# PROIECT_OPEN_READER_v53.net
KiCad netlist of a schematic drawn in EAGLE
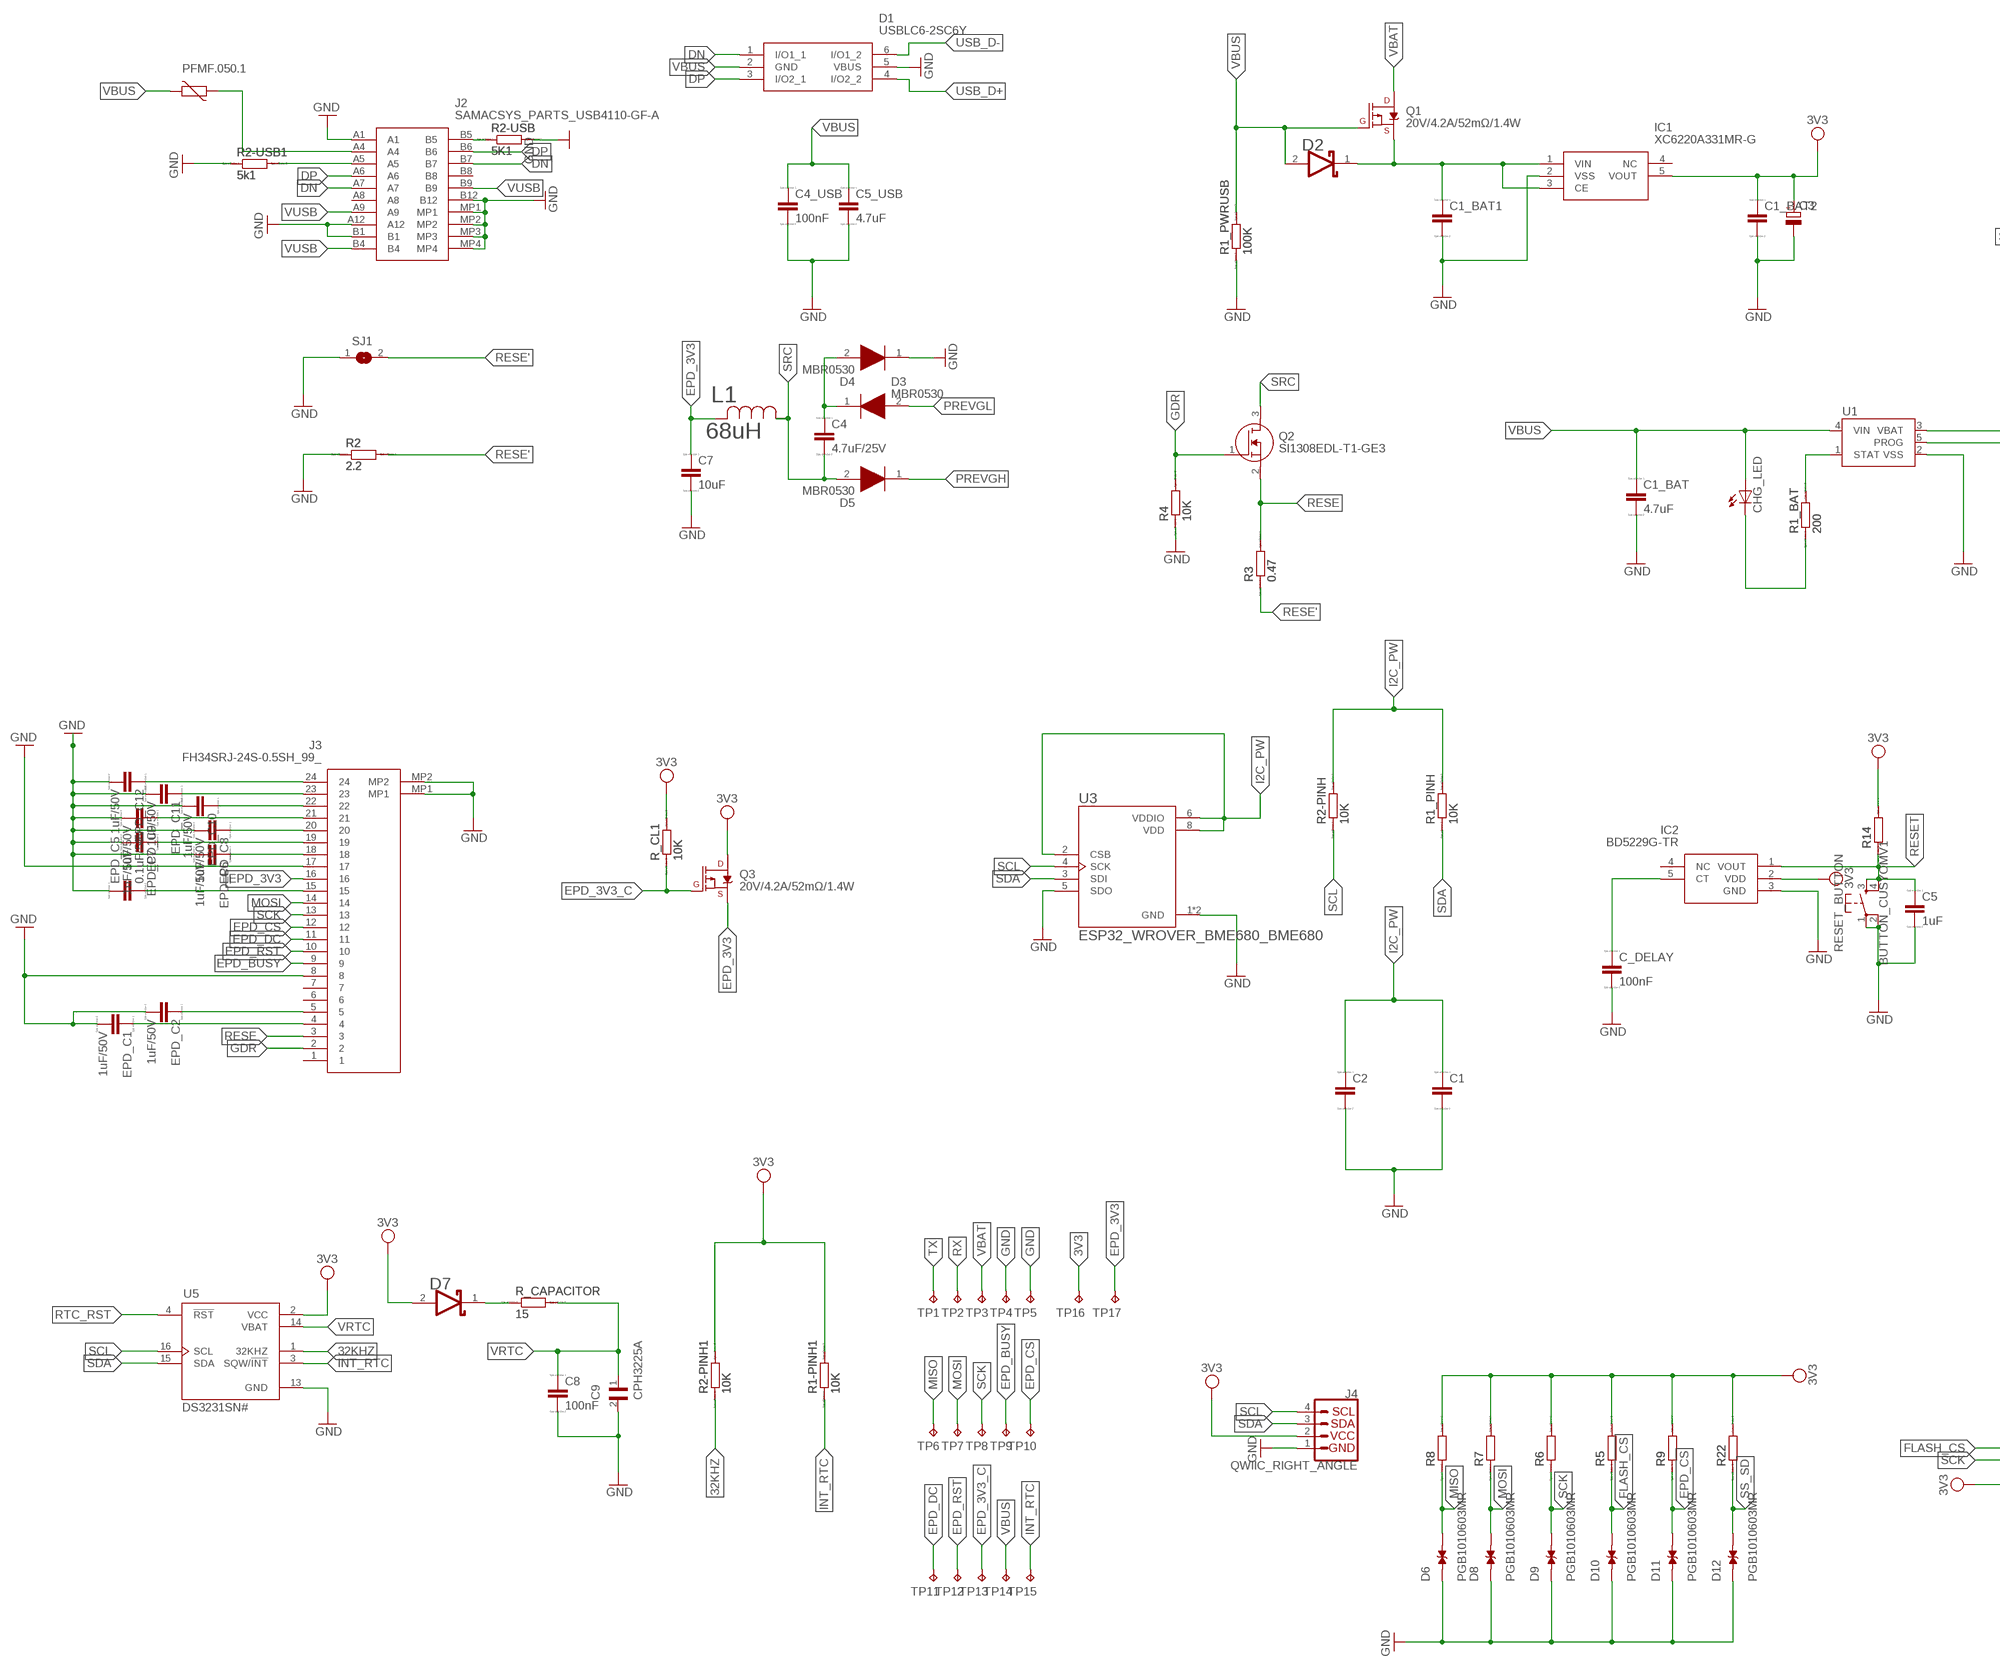
[diagram p0: schematic, sheet 1, part 1 of 2]
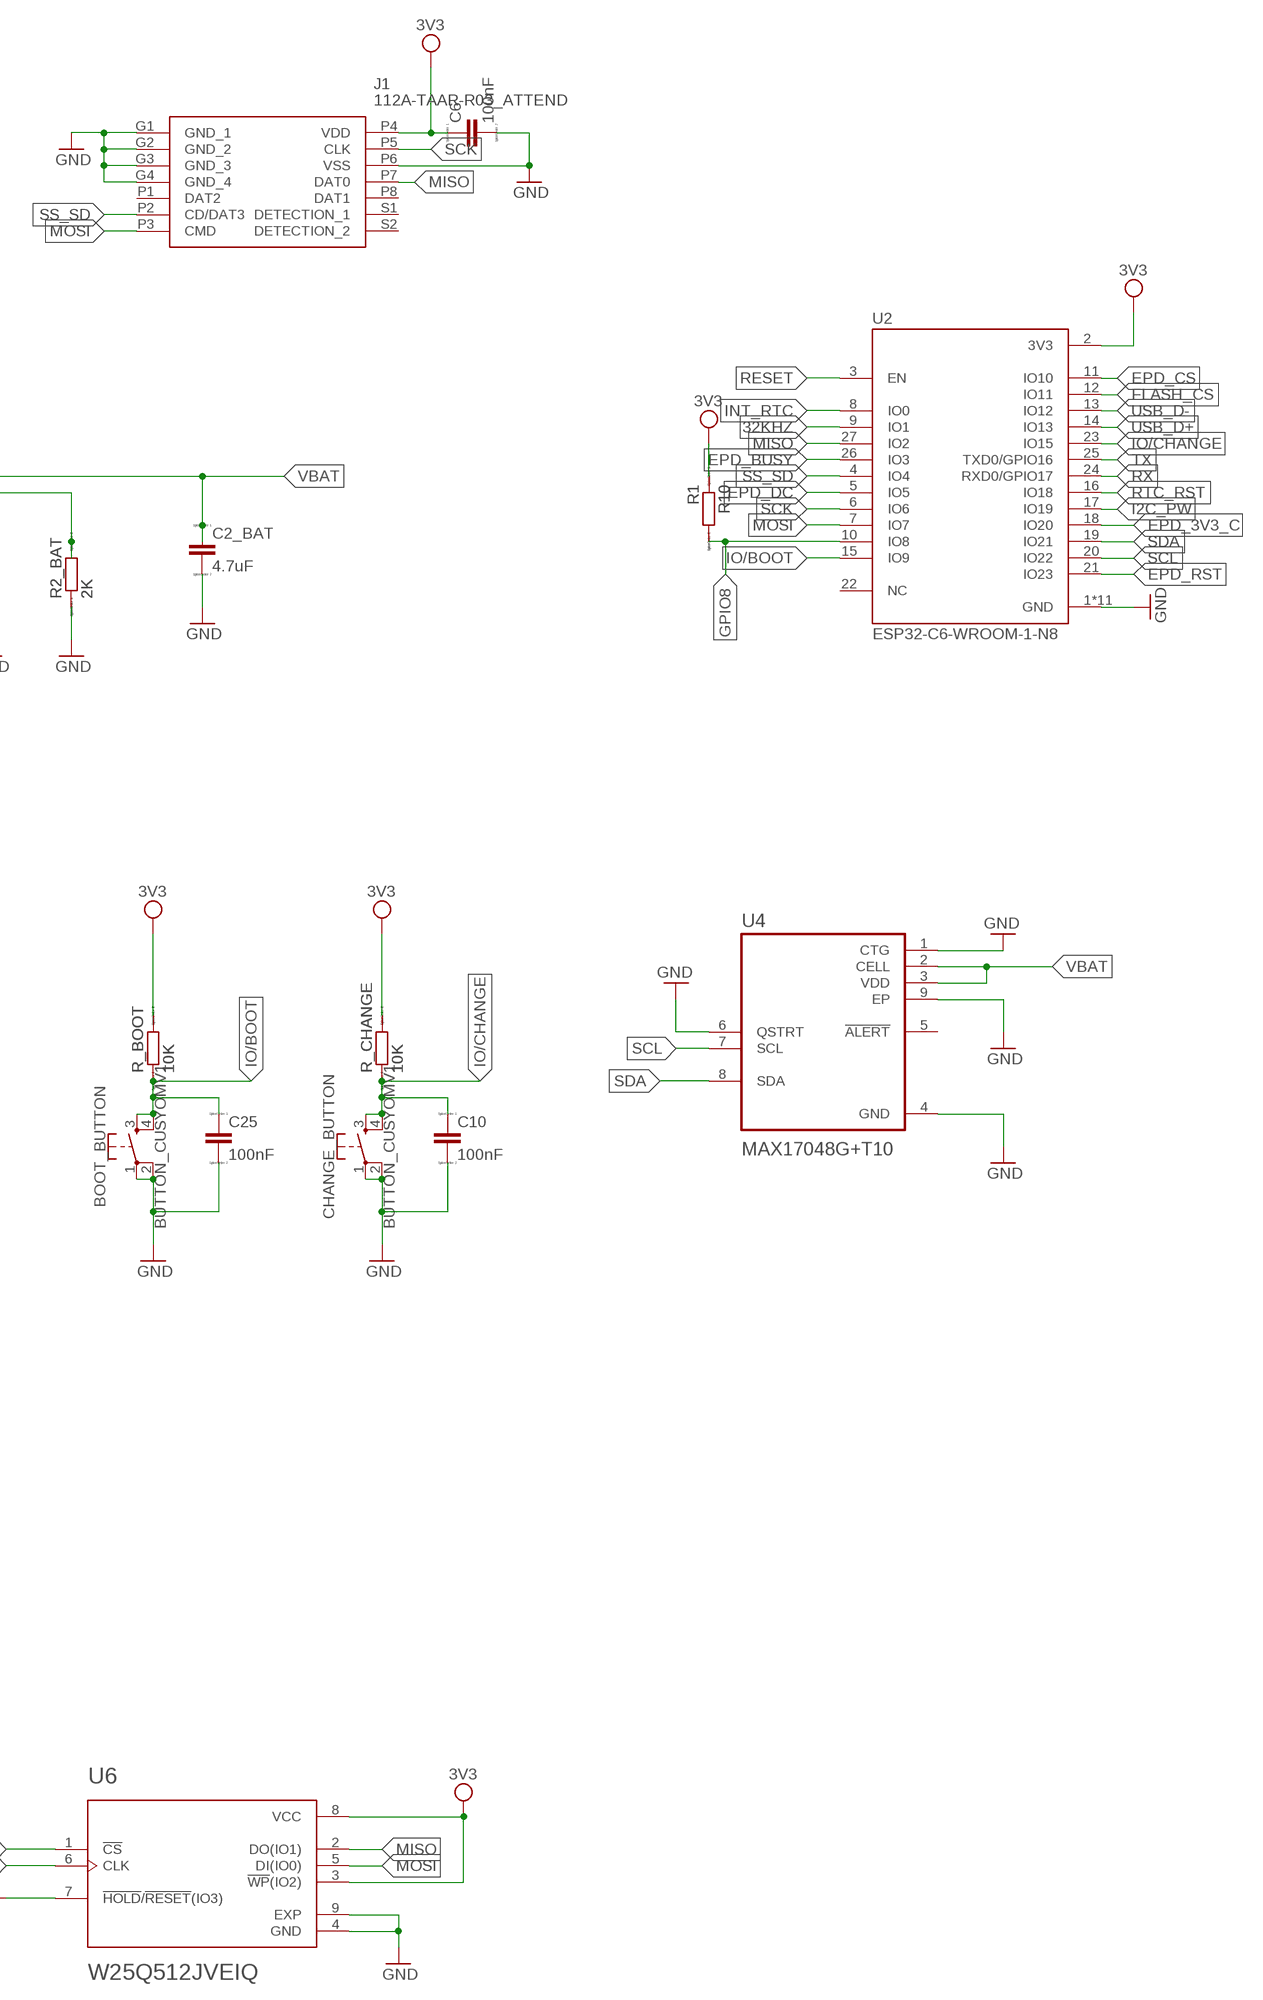
[diagram p1: schematic, sheet 1, part 2 of 2]

(export (version "E")
  (design (tool "Eeschema 10.0.6"))
  (components
    (comp (ref "BOOT_BUTTON")
      (value "BUTTON_CUSYOMV1")
      (footprint "eagle-import:MYBUTTON")
      (libsource (lib "eagle-import") (part "BUTTON_CUSYOMV1"))
    )
    (comp (ref "C1")
      (value "EAGLE-LTSPICE_CC0402")
      (footprint "eagle-import:EAGLE-LTSPICE_C0402")
      (libsource (lib "eagle-import") (part "EAGLE-LTSPICE_CC0402"))
    )
    (comp (ref "C1_BAT")
      (value "4.7uF")
      (footprint "eagle-import:EAGLE-LTSPICE_C0402")
      (libsource (lib "eagle-import") (part "EAGLE-LTSPICE_CC0402"))
    )
    (comp (ref "C1_BAT1")
      (value "EAGLE-LTSPICE_CC0402")
      (footprint "eagle-import:EAGLE-LTSPICE_C0402")
      (libsource (lib "eagle-import") (part "EAGLE-LTSPICE_CC0402"))
    )
    (comp (ref "C1_BAT2")
      (value "EAGLE-LTSPICE_CC0402")
      (footprint "eagle-import:EAGLE-LTSPICE_C0402")
      (libsource (lib "eagle-import") (part "EAGLE-LTSPICE_CC0402"))
    )
    (comp (ref "C2")
      (value "EAGLE-LTSPICE_CC0402")
      (footprint "eagle-import:EAGLE-LTSPICE_C0402")
      (libsource (lib "eagle-import") (part "EAGLE-LTSPICE_CC0402"))
    )
    (comp (ref "C2_BAT")
      (value "4.7uF")
      (footprint "eagle-import:EAGLE-LTSPICE_C0402")
      (libsource (lib "eagle-import") (part "EAGLE-LTSPICE_CC0402"))
    )
    (comp (ref "C3")
      (value "RCL_CPOL-EUCT3528")
      (footprint "eagle-import:RCL_CT3528")
      (libsource (lib "eagle-import") (part "RCL_CPOL-EUCT3528"))
    )
    (comp (ref "C4")
      (value "4.7uF/25V")
      (footprint "eagle-import:EAGLE-LTSPICE_C0402")
      (libsource (lib "eagle-import") (part "EAGLE-LTSPICE_CC0402"))
    )
    (comp (ref "C4_USB")
      (value "100nF")
      (footprint "eagle-import:EAGLE-LTSPICE_C0402")
      (libsource (lib "eagle-import") (part "EAGLE-LTSPICE_CC0402"))
    )
    (comp (ref "C5")
      (value "1uF")
      (footprint "eagle-import:EAGLE-LTSPICE_C0402")
      (libsource (lib "eagle-import") (part "EAGLE-LTSPICE_CC0402"))
    )
    (comp (ref "C5_USB")
      (value "4.7uF")
      (footprint "eagle-import:EAGLE-LTSPICE_C0402")
      (libsource (lib "eagle-import") (part "EAGLE-LTSPICE_CC0402"))
    )
    (comp (ref "C6")
      (value "100nF")
      (footprint "eagle-import:EAGLE-LTSPICE_C0402")
      (libsource (lib "eagle-import") (part "EAGLE-LTSPICE_CC0402"))
    )
    (comp (ref "C7")
      (value "10uF")
      (footprint "eagle-import:EAGLE-LTSPICE_C0402")
      (libsource (lib "eagle-import") (part "EAGLE-LTSPICE_CC0402"))
    )
    (comp (ref "C8")
      (value "100nF")
      (footprint "eagle-import:EAGLE-LTSPICE_C0402")
      (libsource (lib "eagle-import") (part "EAGLE-LTSPICE_CC0402"))
    )
    (comp (ref "C9")
      (value "CPH3225A")
      (footprint "eagle-import:CAPCP3225X100N")
      (fields (field (name "MF") "Seiko Instruments"))
      (libsource (lib "eagle-import") (part "CPH3225A"))
    )
    (comp (ref "C10")
      (value "100nF")
      (footprint "eagle-import:EAGLE-LTSPICE_C0402")
      (libsource (lib "eagle-import") (part "EAGLE-LTSPICE_CC0402"))
    )
    (comp (ref "C25")
      (value "100nF")
      (footprint "eagle-import:EAGLE-LTSPICE_C0402")
      (libsource (lib "eagle-import") (part "EAGLE-LTSPICE_CC0402"))
    )
    (comp (ref "CHANGE_BUTTON")
      (value "BUTTON_CUSYOMV1")
      (footprint "eagle-import:MYBUTTON")
      (libsource (lib "eagle-import") (part "BUTTON_CUSYOMV1"))
    )
    (comp (ref "CHG_LED")
      (value "ADAFRUIT_LEDCHIP-LED0603")
      (footprint "eagle-import:ADAFRUIT_CHIP-LED0603")
      (libsource (lib "eagle-import") (part "ADAFRUIT_LEDCHIP-LED0603"))
    )
    (comp (ref "C_DELAY")
      (value "100nF")
      (footprint "eagle-import:EAGLE-LTSPICE_C0402")
      (libsource (lib "eagle-import") (part "EAGLE-LTSPICE_CC0402"))
    )
    (comp (ref "D1")
      (value "USBLC6-2SC6Y")
      (footprint "eagle-import:SOT95P280X145-6N")
      (fields (field (name "MF") "STMicroelectronics"))
      (libsource (lib "eagle-import") (part "USBLC6-2SC6Y"))
    )
    (comp (ref "D2")
      (value "ESP32_WROVER_AVX---SD0805S020S1R0_AVX_SD0805S020S1R0_0_0AVX_SD0805S020S1R0_0_0")
      (footprint "eagle-import:ESP32_WROVER_AVX---SD0805S020S1R0_AVX_SD0805S020S1R0_0")
      (fields
        (field (name "DIGIKEY_PART_NUMBER") "478-7800-1-ND")
        (field (name "MF") "AVX")
        (field (name "MOUSER_PART_NUMBER") "581-SD0805S020S1R0")
      )
      (libsource (lib "eagle-import") (part "ESP32_WROVER_AVX---SD0805S020S1R0_AVX_SD0805S020S1R0_0_0AVX_SD0805S020S1R0_0_0"))
    )
    (comp (ref "D3")
      (value "MBR0530")
      (footprint "eagle-import:SOD3716X135N")
      (fields (field (name "MF") "ON Semiconductor"))
      (libsource (lib "eagle-import") (part "MBR0530"))
    )
    (comp (ref "D4")
      (value "MBR0530")
      (footprint "eagle-import:SOD3716X135N")
      (fields (field (name "MF") "ON Semiconductor"))
      (libsource (lib "eagle-import") (part "MBR0530"))
    )
    (comp (ref "D5")
      (value "MBR0530")
      (footprint "eagle-import:SOD3716X135N")
      (fields (field (name "MF") "ON Semiconductor"))
      (libsource (lib "eagle-import") (part "MBR0530"))
    )
    (comp (ref "D6")
      (value "PGB1010603MR")
      (footprint "eagle-import:DIOC1608X36N")
      (fields (field (name "MF") "Littelfuse Inc."))
      (libsource (lib "eagle-import") (part "PGB1010603MR"))
    )
    (comp (ref "D7")
      (value "ESP32_WROVER_AVX---SD0805S020S1R0_AVX_SD0805S020S1R0_0_0AVX_SD0805S020S1R0_0_0")
      (footprint "eagle-import:ESP32_WROVER_AVX---SD0805S020S1R0_AVX_SD0805S020S1R0_0")
      (fields
        (field (name "DIGIKEY_PART_NUMBER") "478-7800-1-ND")
        (field (name "MF") "AVX")
        (field (name "MOUSER_PART_NUMBER") "581-SD0805S020S1R0")
      )
      (libsource (lib "eagle-import") (part "ESP32_WROVER_AVX---SD0805S020S1R0_AVX_SD0805S020S1R0_0_0AVX_SD0805S020S1R0_0_0"))
    )
    (comp (ref "D8")
      (value "PGB1010603MR")
      (footprint "eagle-import:DIOC1608X36N")
      (fields (field (name "MF") "Littelfuse Inc."))
      (libsource (lib "eagle-import") (part "PGB1010603MR"))
    )
    (comp (ref "D9")
      (value "PGB1010603MR")
      (footprint "eagle-import:DIOC1608X36N")
      (fields (field (name "MF") "Littelfuse Inc."))
      (libsource (lib "eagle-import") (part "PGB1010603MR"))
    )
    (comp (ref "D10")
      (value "PGB1010603MR")
      (footprint "eagle-import:DIOC1608X36N")
      (fields (field (name "MF") "Littelfuse Inc."))
      (libsource (lib "eagle-import") (part "PGB1010603MR"))
    )
    (comp (ref "D11")
      (value "PGB1010603MR")
      (footprint "eagle-import:DIOC1608X36N")
      (fields (field (name "MF") "Littelfuse Inc."))
      (libsource (lib "eagle-import") (part "PGB1010603MR"))
    )
    (comp (ref "D12")
      (value "PGB1010603MR")
      (footprint "eagle-import:DIOC1608X36N")
      (fields (field (name "MF") "Littelfuse Inc."))
      (libsource (lib "eagle-import") (part "PGB1010603MR"))
    )
    (comp (ref "EPD_C1")
      (value "1uF/50V")
      (footprint "eagle-import:EAGLE-LTSPICE_C0402")
      (libsource (lib "eagle-import") (part "EAGLE-LTSPICE_CC0402"))
    )
    (comp (ref "EPD_C2")
      (value "1uF/50V")
      (footprint "eagle-import:EAGLE-LTSPICE_C0402")
      (libsource (lib "eagle-import") (part "EAGLE-LTSPICE_CC0402"))
    )
    (comp (ref "EPD_C5")
      (value "0.1uF/50V")
      (footprint "eagle-import:EAGLE-LTSPICE_C0402")
      (libsource (lib "eagle-import") (part "EAGLE-LTSPICE_CC0402"))
    )
    (comp (ref "EPD_C6")
      (value "1uF/50V")
      (footprint "eagle-import:EAGLE-LTSPICE_C0402")
      (libsource (lib "eagle-import") (part "EAGLE-LTSPICE_CC0402"))
    )
    (comp (ref "EPD_C7")
      (value "1uF/50V")
      (footprint "eagle-import:EAGLE-LTSPICE_C0402")
      (libsource (lib "eagle-import") (part "EAGLE-LTSPICE_CC0402"))
    )
    (comp (ref "EPD_C8")
      (value "1uF/50V")
      (footprint "eagle-import:EAGLE-LTSPICE_C0402")
      (libsource (lib "eagle-import") (part "EAGLE-LTSPICE_CC0402"))
    )
    (comp (ref "EPD_C9")
      (value "1uF/50V")
      (footprint "eagle-import:EAGLE-LTSPICE_C0402")
      (libsource (lib "eagle-import") (part "EAGLE-LTSPICE_CC0402"))
    )
    (comp (ref "EPD_C10")
      (value "1uF/50V")
      (footprint "eagle-import:EAGLE-LTSPICE_C0402")
      (libsource (lib "eagle-import") (part "EAGLE-LTSPICE_CC0402"))
    )
    (comp (ref "EPD_C11")
      (value "1uF/50V")
      (footprint "eagle-import:EAGLE-LTSPICE_C0402")
      (libsource (lib "eagle-import") (part "EAGLE-LTSPICE_CC0402"))
    )
    (comp (ref "EPD_C12")
      (value "1uF/50V")
      (footprint "eagle-import:EAGLE-LTSPICE_C0402")
      (libsource (lib "eagle-import") (part "EAGLE-LTSPICE_CC0402"))
    )
    (comp (ref "IC1")
      (value "XC6220A331MR-G")
      (footprint "eagle-import:SOT95P280X120-5N")
      (fields (field (name "MOUSER_PART_NUMBER") "865-XC6220A331MR-G"))
      (libsource (lib "eagle-import") (part "XC6220A331MR-G"))
    )
    (comp (ref "IC2")
      (value "BD5229G-TR")
      (footprint "eagle-import:SOT95P280X125-5N")
      (fields (field (name "MOUSER_PART_NUMBER") "755-BD5229G-TR"))
      (libsource (lib "eagle-import") (part "BD5229G-TR"))
    )
    (comp (ref "J1")
      (value "112A-TAAR-R03_ATTEND")
      (footprint "eagle-import:112ATAARR03ATTEND")
      (fields (field (name "MANUFACTURER_PART_NUMBER") "112A-TAAR-R03 ATTEND"))
      (libsource (lib "eagle-import") (part "112A-TAAR-R03_ATTEND"))
    )
    (comp (ref "J2")
      (value "SAMACSYS_PARTS_USB4110-GF-A")
      (footprint "eagle-import:SAMACSYS_PARTS_USB4110GFA")
      (fields
        (field (name "MANUFACTURER_PART_NUMBER") "USB4110-GF-A")
        (field (name "MOUSER_PART_NUMBER") "640-USB4110-GF-A")
      )
      (libsource (lib "eagle-import") (part "SAMACSYS_PARTS_USB4110-GF-A"))
    )
    (comp (ref "J3")
      (value "FH34SRJ-24S-0.5SH_99_")
      (footprint "eagle-import:FH34SRJ24S05SH99")
      (fields
        (field (name "MANUFACTURER_PART_NUMBER") "FH34SRJ-24S-0.5SH(99)")
        (field (name "MOUSER_PART_NUMBER") "798-FH34SRJ24S05SH99")
      )
      (libsource (lib "eagle-import") (part "FH34SRJ-24S-0.5SH_99_"))
    )
    (comp (ref "J4")
      (value "QWIIC_RIGHT_ANGLE")
      (footprint "eagle-import:JST04_1MM_RA")
      (libsource (lib "eagle-import") (part "QWIIC_CONNECTORJS-1MM"))
    )
    (comp (ref "L1")
      (value "68uH")
      (footprint "eagle-import:IND_4828-WE-TPC_WRE")
      (fields
        (field (name "MANUFACTURER_PART_NUMBER") "744043680")
        (field (name "COPYRIGHT") "Copyright (C) 2024 Ultra Librarian. All rights reserved.")
      )
      (libsource (lib "eagle-import") (part "744043680IND_4828-WE-TPC_WRE"))
    )
    (comp (ref "PFMF.050.1")
      (value "ESP32C6_VARISTORCN1812")
      (footprint "eagle-import:ESP32C6_VARISTOR_CT_CN1812")
      (libsource (lib "eagle-import") (part "ESP32C6_VARISTORCN1812"))
    )
    (comp (ref "Q1")
      (value "20V/4.2A/52mΩ/1.4W")
      (footprint "eagle-import:ESP32_WROVER_SPARKFUN-DISCRETESEMI_SOT23-3")
      (libsource (lib "eagle-import") (part "ESP32_WROVER_SPARKFUN-DISCRETESEMI_MOSFET_PCH-DMG2305UX-7"))
    )
    (comp (ref "Q2")
      (value "SI1308EDL-T1-GE3")
      (footprint "eagle-import:SOT65P210X110-3N")
      (fields (field (name "MF") "Vishay Siliconix"))
      (libsource (lib "eagle-import") (part "SI1308EDL-T1-GE3"))
    )
    (comp (ref "Q3")
      (value "20V/4.2A/52mΩ/1.4W")
      (footprint "eagle-import:ESP32_WROVER_SPARKFUN-DISCRETESEMI_SOT23-3")
      (libsource (lib "eagle-import") (part "ESP32_WROVER_SPARKFUN-DISCRETESEMI_MOSFET_PCH-DMG2305UX-7"))
    )
    (comp (ref "R1-PINH1")
      (value "10K")
      (footprint "eagle-import:ESP32_WROVER_EAGLE-LTSPICE_R0402")
      (libsource (lib "eagle-import") (part "ESP32_WROVER_EAGLE-LTSPICE_RR0402"))
    )
    (comp (ref "R1_BAT")
      (value "200")
      (footprint "eagle-import:ESP32_WROVER_EAGLE-LTSPICE_R0402")
      (libsource (lib "eagle-import") (part "ESP32_WROVER_EAGLE-LTSPICE_RR0402"))
    )
    (comp (ref "R1_PINH")
      (value "10K")
      (footprint "eagle-import:ESP32_WROVER_EAGLE-LTSPICE_R0402")
      (libsource (lib "eagle-import") (part "ESP32_WROVER_EAGLE-LTSPICE_RR0402"))
    )
    (comp (ref "R1_PWRUSB")
      (value "100K")
      (footprint "eagle-import:ESP32_WROVER_EAGLE-LTSPICE_R0402")
      (libsource (lib "eagle-import") (part "ESP32_WROVER_EAGLE-LTSPICE_RR0402"))
    )
    (comp (ref "R2")
      (value "2.2")
      (footprint "eagle-import:ESP32_WROVER_EAGLE-LTSPICE_R0402")
      (libsource (lib "eagle-import") (part "ESP32_WROVER_EAGLE-LTSPICE_RR0402"))
    )
    (comp (ref "R2-PINH")
      (value "10K")
      (footprint "eagle-import:ESP32_WROVER_EAGLE-LTSPICE_R0402")
      (libsource (lib "eagle-import") (part "ESP32_WROVER_EAGLE-LTSPICE_RR0402"))
    )
    (comp (ref "R2-PINH1")
      (value "10K")
      (footprint "eagle-import:ESP32_WROVER_EAGLE-LTSPICE_R0402")
      (libsource (lib "eagle-import") (part "ESP32_WROVER_EAGLE-LTSPICE_RR0402"))
    )
    (comp (ref "R2-USB")
      (value "5K1")
      (footprint "eagle-import:ESP32_WROVER_EAGLE-LTSPICE_R0402")
      (libsource (lib "eagle-import") (part "ESP32_WROVER_EAGLE-LTSPICE_RR0402"))
    )
    (comp (ref "R2-USB1")
      (value "5k1")
      (footprint "eagle-import:ESP32_WROVER_EAGLE-LTSPICE_R0402")
      (libsource (lib "eagle-import") (part "ESP32_WROVER_EAGLE-LTSPICE_RR0402"))
    )
    (comp (ref "R2_BAT")
      (value "2K")
      (footprint "eagle-import:ESP32_WROVER_EAGLE-LTSPICE_R0402")
      (libsource (lib "eagle-import") (part "ESP32_WROVER_EAGLE-LTSPICE_RR0402"))
    )
    (comp (ref "R3")
      (value "0.47")
      (footprint "eagle-import:ESP32_WROVER_EAGLE-LTSPICE_R0402")
      (libsource (lib "eagle-import") (part "ESP32_WROVER_EAGLE-LTSPICE_RR0402"))
    )
    (comp (ref "R4")
      (value "10K")
      (footprint "eagle-import:ESP32_WROVER_EAGLE-LTSPICE_R0402")
      (libsource (lib "eagle-import") (part "ESP32_WROVER_EAGLE-LTSPICE_RR0402"))
    )
    (comp (ref "R5")
      (value "ESP32_WROVER_EAGLE-LTSPICE_RR0402")
      (footprint "eagle-import:ESP32_WROVER_EAGLE-LTSPICE_R0402")
      (libsource (lib "eagle-import") (part "ESP32_WROVER_EAGLE-LTSPICE_RR0402"))
    )
    (comp (ref "R6")
      (value "ESP32_WROVER_EAGLE-LTSPICE_RR0402")
      (footprint "eagle-import:ESP32_WROVER_EAGLE-LTSPICE_R0402")
      (libsource (lib "eagle-import") (part "ESP32_WROVER_EAGLE-LTSPICE_RR0402"))
    )
    (comp (ref "R7")
      (value "ESP32_WROVER_EAGLE-LTSPICE_RR0402")
      (footprint "eagle-import:ESP32_WROVER_EAGLE-LTSPICE_R0402")
      (libsource (lib "eagle-import") (part "ESP32_WROVER_EAGLE-LTSPICE_RR0402"))
    )
    (comp (ref "R8")
      (value "ESP32_WROVER_EAGLE-LTSPICE_RR0402")
      (footprint "eagle-import:ESP32_WROVER_EAGLE-LTSPICE_R0402")
      (libsource (lib "eagle-import") (part "ESP32_WROVER_EAGLE-LTSPICE_RR0402"))
    )
    (comp (ref "R9")
      (value "ESP32_WROVER_EAGLE-LTSPICE_RR0402")
      (footprint "eagle-import:ESP32_WROVER_EAGLE-LTSPICE_R0402")
      (libsource (lib "eagle-import") (part "ESP32_WROVER_EAGLE-LTSPICE_RR0402"))
    )
    (comp (ref "R10")
      (value "R1")
      (footprint "eagle-import:ESP32_WROVER_EAGLE-LTSPICE_R0402")
      (libsource (lib "eagle-import") (part "ESP32_WROVER_EAGLE-LTSPICE_RR0402"))
    )
    (comp (ref "R14")
      (value "ESP32_WROVER_EAGLE-LTSPICE_RR0402")
      (footprint "eagle-import:ESP32_WROVER_EAGLE-LTSPICE_R0402")
      (libsource (lib "eagle-import") (part "ESP32_WROVER_EAGLE-LTSPICE_RR0402"))
    )
    (comp (ref "R22")
      (value "ESP32_WROVER_EAGLE-LTSPICE_RR0402")
      (footprint "eagle-import:ESP32_WROVER_EAGLE-LTSPICE_R0402")
      (libsource (lib "eagle-import") (part "ESP32_WROVER_EAGLE-LTSPICE_RR0402"))
    )
    (comp (ref "RESET_BUTTON")
      (value "BUTTON_CUSYOMV1")
      (footprint "eagle-import:MYBUTTON")
      (libsource (lib "eagle-import") (part "BUTTON_CUSYOMV1"))
    )
    (comp (ref "R_BOOT")
      (value "10K")
      (footprint "eagle-import:ESP32_WROVER_EAGLE-LTSPICE_R0402")
      (libsource (lib "eagle-import") (part "ESP32_WROVER_EAGLE-LTSPICE_RR0402"))
    )
    (comp (ref "R_CAPACITOR")
      (value "15")
      (footprint "eagle-import:ESP32_WROVER_EAGLE-LTSPICE_R0402")
      (libsource (lib "eagle-import") (part "ESP32_WROVER_EAGLE-LTSPICE_RR0402"))
    )
    (comp (ref "R_CHANGE")
      (value "10K")
      (footprint "eagle-import:ESP32_WROVER_EAGLE-LTSPICE_R0402")
      (libsource (lib "eagle-import") (part "ESP32_WROVER_EAGLE-LTSPICE_RR0402"))
    )
    (comp (ref "R_CL1")
      (value "10K")
      (footprint "eagle-import:ESP32_WROVER_EAGLE-LTSPICE_R0402")
      (libsource (lib "eagle-import") (part "ESP32_WROVER_EAGLE-LTSPICE_RR0402"))
    )
    (comp (ref "SJ1") (value "SJ") (footprint "eagle-import:SJ") (libsource (lib "eagle-import") (part "SJ")))
    (comp (ref "TP1")
      (value "TPTP20R")
      (footprint "eagle-import:TP20R")
      (libsource (lib "eagle-import") (part "TPTP20R"))
    )
    (comp (ref "TP2")
      (value "TPTP20R")
      (footprint "eagle-import:TP20R")
      (libsource (lib "eagle-import") (part "TPTP20R"))
    )
    (comp (ref "TP3")
      (value "TPTP20R")
      (footprint "eagle-import:TP20R")
      (libsource (lib "eagle-import") (part "TPTP20R"))
    )
    (comp (ref "TP4")
      (value "TPTP20R")
      (footprint "eagle-import:TP20R")
      (libsource (lib "eagle-import") (part "TPTP20R"))
    )
    (comp (ref "TP5")
      (value "TPTP20R")
      (footprint "eagle-import:TP20R")
      (libsource (lib "eagle-import") (part "TPTP20R"))
    )
    (comp (ref "TP6")
      (value "TPTP20R")
      (footprint "eagle-import:TP20R")
      (libsource (lib "eagle-import") (part "TPTP20R"))
    )
    (comp (ref "TP7")
      (value "TPTP20R")
      (footprint "eagle-import:TP20R")
      (libsource (lib "eagle-import") (part "TPTP20R"))
    )
    (comp (ref "TP8")
      (value "TPTP20R")
      (footprint "eagle-import:TP20R")
      (libsource (lib "eagle-import") (part "TPTP20R"))
    )
    (comp (ref "TP9")
      (value "TPTP20R")
      (footprint "eagle-import:TP20R")
      (libsource (lib "eagle-import") (part "TPTP20R"))
    )
    (comp (ref "TP10")
      (value "TPTP20R")
      (footprint "eagle-import:TP20R")
      (libsource (lib "eagle-import") (part "TPTP20R"))
    )
    (comp (ref "TP11")
      (value "TPTP20R")
      (footprint "eagle-import:TP20R")
      (libsource (lib "eagle-import") (part "TPTP20R"))
    )
    (comp (ref "TP12")
      (value "TPTP20R")
      (footprint "eagle-import:TP20R")
      (libsource (lib "eagle-import") (part "TPTP20R"))
    )
    (comp (ref "TP13")
      (value "TPTP20R")
      (footprint "eagle-import:TP20R")
      (libsource (lib "eagle-import") (part "TPTP20R"))
    )
    (comp (ref "TP14")
      (value "TPTP20R")
      (footprint "eagle-import:TP20R")
      (libsource (lib "eagle-import") (part "TPTP20R"))
    )
    (comp (ref "TP15")
      (value "TPTP20R")
      (footprint "eagle-import:TP20R")
      (libsource (lib "eagle-import") (part "TPTP20R"))
    )
    (comp (ref "TP16")
      (value "TPTP20R")
      (footprint "eagle-import:TP20R")
      (libsource (lib "eagle-import") (part "TPTP20R"))
    )
    (comp (ref "TP17")
      (value "TPTP20R")
      (footprint "eagle-import:TP20R")
      (libsource (lib "eagle-import") (part "TPTP20R"))
    )
    (comp (ref "U1")
      (value "ESP32_WROVER_SPARKFUN-IC-POWER_MCP73831")
      (footprint "eagle-import:ESP32_WROVER_SPARKFUN-IC-POWER_SOT23-5")
      (libsource (lib "eagle-import") (part "ESP32_WROVER_SPARKFUN-IC-POWER_MCP73831"))
    )
    (comp (ref "U2")
      (value "ESP32-C6-WROOM-1-N8")
      (footprint "eagle-import:XCVR_ESP32-C6-WROOM-1-N8")
      (fields (field (name "MF") "Espressif Systems"))
      (libsource (lib "eagle-import") (part "ESP32-C6-WROOM-1-N8"))
    )
    (comp (ref "U3")
      (value "ESP32_WROVER_BME680_BME680")
      (footprint "eagle-import:ESP32_WROVER_BME680_PSON80P300X300X100-8N")
      (fields (field (name "MF") "Bosch Sensortec") (field (name "MP") "BME680"))
      (libsource (lib "eagle-import") (part "ESP32_WROVER_BME680_BME680"))
    )
    (comp (ref "U4")
      (value "MAX17048G+T10")
      (footprint "eagle-import:SON50P200X200X80-9N")
      (fields (field (name "MF") "Analog Devices"))
      (libsource (lib "eagle-import") (part "MAX17048G+T10"))
    )
    (comp (ref "U5")
      (value "DS3231SN#")
      (footprint "eagle-import:SOIC127P1032X265-16N")
      (fields (field (name "MF") "Analog Devices"))
      (libsource (lib "eagle-import") (part "DS3231SN#"))
    )
    (comp (ref "U6")
      (value "W25Q512JVEIQ")
      (footprint "eagle-import:SON127P600X800X80-9N")
      (fields (field (name "MF") "Winbond Electronics"))
      (libsource (lib "eagle-import") (part "W25Q512JVEIQ"))
    )
  )
  (nets
    (net (code "1") (name "3V3") (class "Default")
      (node (ref "C1_BAT2") (pin "1") (pinfunction "1_1") (pintype "passive"))
      (node (ref "C3") (pin "+") (pinfunction "+_+") (pintype "passive"))
      (node (ref "C6") (pin "1") (pinfunction "1_1") (pintype "passive"))
      (node (ref "D7") (pin "2") (pinfunction "ANODE_2") (pintype "bidirectional"))
      (node (ref "IC1") (pin "5") (pinfunction "VOUT_5") (pintype "bidirectional"))
      (node (ref "IC2") (pin "2") (pinfunction "VDD_2") (pintype "bidirectional"))
      (node (ref "J1") (pin "P4") (pinfunction "VDD_P4") (pintype "bidirectional"))
      (node (ref "J4") (pin "2") (pinfunction "2_2") (pintype "power_in"))
      (node (ref "Q3") (pin "3") (pinfunction "D_3") (pintype "bidirectional"))
      (node (ref "R1-PINH1") (pin "2") (pinfunction "2_2") (pintype "passive"))
      (node (ref "R10") (pin "1") (pinfunction "1_1") (pintype "passive"))
      (node (ref "R14") (pin "2") (pinfunction "2_2") (pintype "passive"))
      (node (ref "R2-PINH1") (pin "2") (pinfunction "2_2") (pintype "passive"))
      (node (ref "R22") (pin "2") (pinfunction "2_2") (pintype "passive"))
      (node (ref "R5") (pin "2") (pinfunction "2_2") (pintype "passive"))
      (node (ref "R6") (pin "2") (pinfunction "2_2") (pintype "passive"))
      (node (ref "R7") (pin "2") (pinfunction "2_2") (pintype "passive"))
      (node (ref "R8") (pin "2") (pinfunction "2_2") (pintype "passive"))
      (node (ref "R9") (pin "2") (pinfunction "2_2") (pintype "passive"))
      (node (ref "R_BOOT") (pin "2") (pinfunction "2_2") (pintype "passive"))
      (node (ref "R_CHANGE") (pin "2") (pinfunction "2_2") (pintype "passive"))
      (node (ref "R_CL1") (pin "2") (pinfunction "2_2") (pintype "passive"))
      (node (ref "TP16") (pin "TP") (pinfunction "TP_TP") (pintype "input"))
      (node (ref "U2") (pin "2") (pinfunction "3V3_2") (pintype "power_in"))
      (node (ref "U5") (pin "2") (pinfunction "VCC_2") (pintype "power_in"))
      (node (ref "U6") (pin "3") (pinfunction "~{WP}(IO2)_3") (pintype "bidirectional"))
      (node (ref "U6") (pin "7") (pinfunction "~{HOLD}/~{RESET}(IO3)_7") (pintype "bidirectional"))
      (node (ref "U6") (pin "8") (pinfunction "VCC_8") (pintype "power_in"))
    )
    (net (code "2") (name "32KHZ") (class "Default")
      (node (ref "R2-PINH1") (pin "1") (pinfunction "1_1") (pintype "passive"))
      (node (ref "U2") (pin "9") (pinfunction "IO1_9") (pintype "bidirectional"))
      (node (ref "U5") (pin "1") (pinfunction "32KHZ_1") (pintype "output"))
    )
    (net (code "3") (name "DN") (class "Default")
      (node (ref "D1") (pin "1") (pinfunction "I/O1_1_1") (pintype "bidirectional"))
      (node (ref "J2") (pin "A7") (pinfunction "A7_A7") (pintype "bidirectional"))
      (node (ref "J2") (pin "B7") (pinfunction "B7_B7") (pintype "bidirectional"))
    )
    (net (code "4") (name "DP") (class "Default")
      (node (ref "D1") (pin "3") (pinfunction "I/O2_1_3") (pintype "bidirectional"))
      (node (ref "J2") (pin "A6") (pinfunction "A6_A6") (pintype "bidirectional"))
      (node (ref "J2") (pin "B6") (pinfunction "B6_B6") (pintype "bidirectional"))
    )
    (net (code "5") (name "EPD_3V3") (class "Default")
      (node (ref "C7") (pin "1") (pinfunction "1_1") (pintype "passive"))
      (node (ref "J3") (pin "16") (pinfunction "16_16") (pintype "bidirectional"))
      (node (ref "L1") (pin "2") (pinfunction "2_2") (pintype "passive"))
      (node (ref "Q3") (pin "2") (pinfunction "S_2") (pintype "bidirectional"))
      (node (ref "TP17") (pin "TP") (pinfunction "TP_TP") (pintype "input"))
    )
    (net (code "6") (name "EPD_3V3_C") (class "Default")
      (node (ref "Q3") (pin "1") (pinfunction "G_1") (pintype "bidirectional"))
      (node (ref "R_CL1") (pin "1") (pinfunction "1_1") (pintype "passive"))
      (node (ref "TP13") (pin "TP") (pinfunction "TP_TP") (pintype "input"))
      (node (ref "U2") (pin "18") (pinfunction "IO20_18") (pintype "bidirectional"))
    )
    (net (code "7") (name "EPD_BUSY") (class "Default")
      (node (ref "J3") (pin "9") (pinfunction "9_9") (pintype "bidirectional"))
      (node (ref "TP9") (pin "TP") (pinfunction "TP_TP") (pintype "input"))
      (node (ref "U2") (pin "26") (pinfunction "IO3_26") (pintype "bidirectional"))
    )
    (net (code "8") (name "EPD_CS") (class "Default")
      (node (ref "D11") (pin "2") (pinfunction "2_2") (pintype "passive"))
      (node (ref "J3") (pin "12") (pinfunction "12_12") (pintype "bidirectional"))
      (node (ref "R9") (pin "1") (pinfunction "1_1") (pintype "passive"))
      (node (ref "TP10") (pin "TP") (pinfunction "TP_TP") (pintype "input"))
      (node (ref "U2") (pin "11") (pinfunction "IO10_11") (pintype "bidirectional"))
    )
    (net (code "9") (name "EPD_DC") (class "Default")
      (node (ref "J3") (pin "11") (pinfunction "11_11") (pintype "bidirectional"))
      (node (ref "TP11") (pin "TP") (pinfunction "TP_TP") (pintype "input"))
      (node (ref "U2") (pin "5") (pinfunction "IO5_5") (pintype "bidirectional"))
    )
    (net (code "10") (name "EPD_RST") (class "Default")
      (node (ref "J3") (pin "10") (pinfunction "10_10") (pintype "bidirectional"))
      (node (ref "TP12") (pin "TP") (pinfunction "TP_TP") (pintype "input"))
      (node (ref "U2") (pin "21") (pinfunction "IO23_21") (pintype "bidirectional"))
    )
    (net (code "11") (name "FLASH_CS") (class "Default")
      (node (ref "D10") (pin "2") (pinfunction "2_2") (pintype "passive"))
      (node (ref "R5") (pin "1") (pinfunction "1_1") (pintype "passive"))
      (node (ref "U2") (pin "12") (pinfunction "IO11_12") (pintype "bidirectional"))
      (node (ref "U6") (pin "1") (pinfunction "~{CS}_1") (pintype "input"))
    )
    (net (code "12") (name "GDR") (class "Default")
      (node (ref "J3") (pin "2") (pinfunction "2_2") (pintype "bidirectional"))
      (node (ref "Q2") (pin "1") (pinfunction "G_1") (pintype "bidirectional"))
      (node (ref "R4") (pin "2") (pinfunction "2_2") (pintype "passive"))
    )
    (net (code "13") (name "GND") (class "Default")
      (node (ref "BOOT_BUTTON") (pin "1") (pinfunction "1_1") (pintype "passive"))
      (node (ref "BOOT_BUTTON") (pin "2") (pinfunction "2_2") (pintype "passive"))
      (node (ref "C1") (pin "2") (pinfunction "2_2") (pintype "passive"))
      (node (ref "C10") (pin "2") (pinfunction "2_2") (pintype "passive"))
      (node (ref "C1_BAT") (pin "2") (pinfunction "2_2") (pintype "passive"))
      (node (ref "C1_BAT1") (pin "2") (pinfunction "2_2") (pintype "passive"))
      (node (ref "C1_BAT2") (pin "2") (pinfunction "2_2") (pintype "passive"))
      (node (ref "C2") (pin "2") (pinfunction "2_2") (pintype "passive"))
      (node (ref "C25") (pin "2") (pinfunction "2_2") (pintype "passive"))
      (node (ref "C2_BAT") (pin "2") (pinfunction "2_2") (pintype "passive"))
      (node (ref "C3") (pin "-") (pinfunction "-_-") (pintype "passive"))
      (node (ref "C4_USB") (pin "2") (pinfunction "2_2") (pintype "passive"))
      (node (ref "C5") (pin "2") (pinfunction "2_2") (pintype "passive"))
      (node (ref "C5_USB") (pin "2") (pinfunction "2_2") (pintype "passive"))
      (node (ref "C6") (pin "2") (pinfunction "2_2") (pintype "passive"))
      (node (ref "C7") (pin "2") (pinfunction "2_2") (pintype "passive"))
      (node (ref "C8") (pin "2") (pinfunction "2_2") (pintype "passive"))
      (node (ref "C9") (pin "2") (pinfunction "2_2") (pintype "passive"))
      (node (ref "CHANGE_BUTTON") (pin "1") (pinfunction "1_1") (pintype "passive"))
      (node (ref "CHANGE_BUTTON") (pin "2") (pinfunction "2_2") (pintype "passive"))
      (node (ref "C_DELAY") (pin "2") (pinfunction "2_2") (pintype "passive"))
      (node (ref "D1") (pin "5") (pinfunction "VBUS_5") (pintype "bidirectional"))
      (node (ref "D10") (pin "1") (pinfunction "1_1") (pintype "passive"))
      (node (ref "D11") (pin "1") (pinfunction "1_1") (pintype "passive"))
      (node (ref "D12") (pin "1") (pinfunction "1_1") (pintype "passive"))
      (node (ref "D4") (pin "1") (pinfunction "K_1") (pintype "bidirectional"))
      (node (ref "D6") (pin "1") (pinfunction "1_1") (pintype "passive"))
      (node (ref "D8") (pin "1") (pinfunction "1_1") (pintype "passive"))
      (node (ref "D9") (pin "1") (pinfunction "1_1") (pintype "passive"))
      (node (ref "EPD_C1") (pin "2") (pinfunction "2_2") (pintype "passive"))
      (node (ref "EPD_C10") (pin "2") (pinfunction "2_2") (pintype "passive"))
      (node (ref "EPD_C11") (pin "2") (pinfunction "2_2") (pintype "passive"))
      (node (ref "EPD_C12") (pin "2") (pinfunction "2_2") (pintype "passive"))
      (node (ref "EPD_C2") (pin "2") (pinfunction "2_2") (pintype "passive"))
      (node (ref "EPD_C5") (pin "1") (pinfunction "1_1") (pintype "passive"))
      (node (ref "EPD_C6") (pin "2") (pinfunction "2_2") (pintype "passive"))
      (node (ref "EPD_C7") (pin "2") (pinfunction "2_2") (pintype "passive"))
      (node (ref "EPD_C8") (pin "2") (pinfunction "2_2") (pintype "passive"))
      (node (ref "EPD_C9") (pin "2") (pinfunction "2_2") (pintype "passive"))
      (node (ref "IC1") (pin "2") (pinfunction "VSS_2") (pintype "bidirectional"))
      (node (ref "IC2") (pin "3") (pinfunction "GND_3") (pintype "bidirectional"))
      (node (ref "J1") (pin "G1") (pinfunction "GND_1_G1") (pintype "bidirectional"))
      (node (ref "J1") (pin "G2") (pinfunction "GND_2_G2") (pintype "bidirectional"))
      (node (ref "J1") (pin "G3") (pinfunction "GND_3_G3") (pintype "bidirectional"))
      (node (ref "J1") (pin "G4") (pinfunction "GND_4_G4") (pintype "bidirectional"))
      (node (ref "J1") (pin "P6") (pinfunction "VSS_P6") (pintype "bidirectional"))
      (node (ref "J2") (pin "A1") (pinfunction "A1_A1") (pintype "bidirectional"))
      (node (ref "J2") (pin "A12") (pinfunction "A12_A12") (pintype "bidirectional"))
      (node (ref "J2") (pin "B1") (pinfunction "B1_B1") (pintype "bidirectional"))
      (node (ref "J2") (pin "B12") (pinfunction "B12_B12") (pintype "bidirectional"))
      (node (ref "J2") (pin "MP1") (pinfunction "MP1_MP1") (pintype "bidirectional"))
      (node (ref "J2") (pin "MP2") (pinfunction "MP2_MP2") (pintype "bidirectional"))
      (node (ref "J2") (pin "MP3") (pinfunction "MP3_MP3") (pintype "bidirectional"))
      (node (ref "J2") (pin "MP4") (pinfunction "MP4_MP4") (pintype "bidirectional"))
      (node (ref "J3") (pin "17") (pinfunction "17_17") (pintype "bidirectional"))
      (node (ref "J3") (pin "8") (pinfunction "8_8") (pintype "bidirectional"))
      (node (ref "J3") (pin "MP1") (pinfunction "MP1_MP1") (pintype "bidirectional"))
      (node (ref "J3") (pin "MP2") (pinfunction "MP2_MP2") (pintype "bidirectional"))
      (node (ref "J4") (pin "1") (pinfunction "1_1") (pintype "power_in"))
      (node (ref "R1_PWRUSB") (pin "1") (pinfunction "1_1") (pintype "passive"))
      (node (ref "R2") (pin "1") (pinfunction "1_1") (pintype "passive"))
      (node (ref "R2-USB") (pin "2") (pinfunction "2_2") (pintype "passive"))
      (node (ref "R2-USB1") (pin "1") (pinfunction "1_1") (pintype "passive"))
      (node (ref "R2_BAT") (pin "1") (pinfunction "1_1") (pintype "passive"))
      (node (ref "R4") (pin "1") (pinfunction "1_1") (pintype "passive"))
      (node (ref "RESET_BUTTON") (pin "1") (pinfunction "1_1") (pintype "passive"))
      (node (ref "RESET_BUTTON") (pin "2") (pinfunction "2_2") (pintype "passive"))
      (node (ref "SJ1") (pin "1") (pinfunction "1_1") (pintype "passive"))
      (node (ref "TP4") (pin "TP") (pinfunction "TP_TP") (pintype "input"))
      (node (ref "TP5") (pin "TP") (pinfunction "TP_TP") (pintype "input"))
      (node (ref "U1") (pin "2") (pinfunction "VSS_2") (pintype "power_in"))
      (node (ref "U2") (pin "1") (pinfunction "GND_1") (pintype "power_in"))
      (node (ref "U2") (pin "28") (pinfunction "GND_28") (pintype "power_in"))
      (node (ref "U2") (pin "29_1") (pinfunction "GND_29_1") (pintype "power_in"))
      (node (ref "U2") (pin "29_2") (pinfunction "GND_29_2") (pintype "power_in"))
      (node (ref "U2") (pin "29_3") (pinfunction "GND_29_3") (pintype "power_in"))
      (node (ref "U2") (pin "29_4") (pinfunction "GND_29_4") (pintype "power_in"))
      (node (ref "U2") (pin "29_5") (pinfunction "GND_29_5") (pintype "power_in"))
      (node (ref "U2") (pin "29_6") (pinfunction "GND_29_6") (pintype "power_in"))
      (node (ref "U2") (pin "29_7") (pinfunction "GND_29_7") (pintype "power_in"))
      (node (ref "U2") (pin "29_8") (pinfunction "GND_29_8") (pintype "power_in"))
      (node (ref "U2") (pin "29_9") (pinfunction "GND_29_9") (pintype "power_in"))
      (node (ref "U3") (pin "1") (pinfunction "GND_1") (pintype "power_in"))
      (node (ref "U3") (pin "5") (pinfunction "SDO_5") (pintype "bidirectional"))
      (node (ref "U3") (pin "7") (pinfunction "GND_7") (pintype "power_in"))
      (node (ref "U4") (pin "1") (pinfunction "CTG_1") (pintype "power_in"))
      (node (ref "U4") (pin "4") (pinfunction "GND_4") (pintype "power_in"))
      (node (ref "U4") (pin "6") (pinfunction "QSTRT_6") (pintype "input"))
      (node (ref "U4") (pin "9") (pinfunction "EP_9") (pintype "power_in"))
      (node (ref "U5") (pin "13") (pinfunction "GND_13") (pintype "power_in"))
      (node (ref "U6") (pin "4") (pinfunction "GND_4") (pintype "power_in"))
      (node (ref "U6") (pin "9") (pinfunction "EXP_9") (pintype "passive"))
    )
    (net (code "14") (name "GPIO8") (class "Default")
      (node (ref "R10") (pin "2") (pinfunction "2_2") (pintype "passive"))
      (node (ref "U2") (pin "10") (pinfunction "IO8_10") (pintype "bidirectional"))
    )
    (net (code "15") (name "I2C_PW") (class "Default")
      (node (ref "C1") (pin "1") (pinfunction "1_1") (pintype "passive"))
      (node (ref "C2") (pin "1") (pinfunction "1_1") (pintype "passive"))
      (node (ref "R1_PINH") (pin "2") (pinfunction "2_2") (pintype "passive"))
      (node (ref "R2-PINH") (pin "2") (pinfunction "2_2") (pintype "passive"))
      (node (ref "U2") (pin "17") (pinfunction "IO19_17") (pintype "bidirectional"))
      (node (ref "U3") (pin "2") (pinfunction "CSB_2") (pintype "input"))
      (node (ref "U3") (pin "6") (pinfunction "VDDIO_6") (pintype "power_in"))
      (node (ref "U3") (pin "8") (pinfunction "VDD_8") (pintype "power_in"))
    )
    (net (code "16") (name "INT_RTC") (class "Default")
      (node (ref "R1-PINH1") (pin "1") (pinfunction "1_1") (pintype "passive"))
      (node (ref "TP15") (pin "TP") (pinfunction "TP_TP") (pintype "input"))
      (node (ref "U2") (pin "8") (pinfunction "IO0_8") (pintype "bidirectional"))
      (node (ref "U5") (pin "3") (pinfunction "SQW/~{INT}_3") (pintype "output"))
    )
    (net (code "17") (name "IO{slash}BOOT") (class "Default")
      (node (ref "BOOT_BUTTON") (pin "3") (pinfunction "3_3") (pintype "passive"))
      (node (ref "BOOT_BUTTON") (pin "4") (pinfunction "4_4") (pintype "passive"))
      (node (ref "C25") (pin "1") (pinfunction "1_1") (pintype "passive"))
      (node (ref "R_BOOT") (pin "1") (pinfunction "1_1") (pintype "passive"))
      (node (ref "U2") (pin "15") (pinfunction "IO9_15") (pintype "bidirectional"))
    )
    (net (code "18") (name "IO{slash}CHANGE") (class "Default")
      (node (ref "C10") (pin "1") (pinfunction "1_1") (pintype "passive"))
      (node (ref "CHANGE_BUTTON") (pin "3") (pinfunction "3_3") (pintype "passive"))
      (node (ref "CHANGE_BUTTON") (pin "4") (pinfunction "4_4") (pintype "passive"))
      (node (ref "R_CHANGE") (pin "1") (pinfunction "1_1") (pintype "passive"))
      (node (ref "U2") (pin "23") (pinfunction "IO15_23") (pintype "bidirectional"))
    )
    (net (code "19") (name "MISO") (class "Default")
      (node (ref "D6") (pin "2") (pinfunction "2_2") (pintype "passive"))
      (node (ref "J1") (pin "P7") (pinfunction "DAT0_P7") (pintype "bidirectional"))
      (node (ref "R8") (pin "1") (pinfunction "1_1") (pintype "passive"))
      (node (ref "TP6") (pin "TP") (pinfunction "TP_TP") (pintype "input"))
      (node (ref "U2") (pin "27") (pinfunction "IO2_27") (pintype "bidirectional"))
      (node (ref "U6") (pin "2") (pinfunction "DO(IO1)_2") (pintype "bidirectional"))
    )
    (net (code "20") (name "MOSI") (class "Default")
      (node (ref "D8") (pin "2") (pinfunction "2_2") (pintype "passive"))
      (node (ref "J1") (pin "P3") (pinfunction "CMD_P3") (pintype "bidirectional"))
      (node (ref "J3") (pin "14") (pinfunction "14_14") (pintype "bidirectional"))
      (node (ref "R7") (pin "1") (pinfunction "1_1") (pintype "passive"))
      (node (ref "TP7") (pin "TP") (pinfunction "TP_TP") (pintype "input"))
      (node (ref "U2") (pin "7") (pinfunction "IO7_7") (pintype "bidirectional"))
      (node (ref "U6") (pin "5") (pinfunction "DI(IO0)_5") (pintype "bidirectional"))
    )
    (net (code "21") (name "Net-(CHG_LED-PadC)") (class "Default")
      (node (ref "CHG_LED") (pin "C") (pinfunction "C_C") (pintype "passive"))
      (node (ref "R1_BAT") (pin "1") (pinfunction "1_1") (pintype "passive"))
    )
    (net (code "22") (name "Net-(D2-CATHODE)") (class "Default")
      (node (ref "C1_BAT1") (pin "1") (pinfunction "1_1") (pintype "passive"))
      (node (ref "D2") (pin "1") (pinfunction "CATHODE_1") (pintype "bidirectional"))
      (node (ref "IC1") (pin "1") (pinfunction "VIN_1") (pintype "bidirectional"))
      (node (ref "IC1") (pin "3") (pinfunction "CE_3") (pintype "bidirectional"))
      (node (ref "Q1") (pin "2") (pinfunction "S_2") (pintype "bidirectional"))
    )
    (net (code "23") (name "Net-(D3-K)") (class "Default")
      (node (ref "C4") (pin "1") (pinfunction "1_1") (pintype "passive"))
      (node (ref "D3") (pin "1") (pinfunction "K_1") (pintype "bidirectional"))
      (node (ref "D4") (pin "2") (pinfunction "A_2") (pintype "bidirectional"))
    )
    (net (code "24") (name "Net-(D7-CATHODE)") (class "Default")
      (node (ref "D7") (pin "1") (pinfunction "CATHODE_1") (pintype "bidirectional"))
      (node (ref "R_CAPACITOR") (pin "1") (pinfunction "1_1") (pintype "passive"))
    )
    (net (code "25") (name "Net-(EPD_C1-Pad1)") (class "Default")
      (node (ref "EPD_C1") (pin "1") (pinfunction "1_1") (pintype "passive"))
      (node (ref "J3") (pin "4") (pinfunction "4_4") (pintype "bidirectional"))
    )
    (net (code "26") (name "Net-(EPD_C2-Pad1)") (class "Default")
      (node (ref "EPD_C2") (pin "1") (pinfunction "1_1") (pintype "passive"))
      (node (ref "J3") (pin "5") (pinfunction "5_5") (pintype "bidirectional"))
    )
    (net (code "27") (name "Net-(EPD_C5-Pad2)") (class "Default")
      (node (ref "EPD_C5") (pin "2") (pinfunction "2_2") (pintype "passive"))
      (node (ref "J3") (pin "15") (pinfunction "15_15") (pintype "bidirectional"))
    )
    (net (code "28") (name "Net-(EPD_C6-Pad1)") (class "Default")
      (node (ref "EPD_C6") (pin "1") (pinfunction "1_1") (pintype "passive"))
      (node (ref "J3") (pin "18") (pinfunction "18_18") (pintype "bidirectional"))
    )
    (net (code "29") (name "Net-(EPD_C7-Pad1)") (class "Default")
      (node (ref "EPD_C7") (pin "1") (pinfunction "1_1") (pintype "passive"))
      (node (ref "J3") (pin "19") (pinfunction "19_19") (pintype "bidirectional"))
    )
    (net (code "30") (name "Net-(EPD_C8-Pad1)") (class "Default")
      (node (ref "EPD_C8") (pin "1") (pinfunction "1_1") (pintype "passive"))
      (node (ref "J3") (pin "20") (pinfunction "20_20") (pintype "bidirectional"))
    )
    (net (code "31") (name "Net-(EPD_C9-Pad1)") (class "Default")
      (node (ref "EPD_C9") (pin "1") (pinfunction "1_1") (pintype "passive"))
      (node (ref "J3") (pin "21") (pinfunction "21_21") (pintype "bidirectional"))
    )
    (net (code "32") (name "Net-(EPD_C10-Pad1)") (class "Default")
      (node (ref "EPD_C10") (pin "1") (pinfunction "1_1") (pintype "passive"))
      (node (ref "J3") (pin "22") (pinfunction "22_22") (pintype "bidirectional"))
    )
    (net (code "33") (name "Net-(EPD_C11-Pad1)") (class "Default")
      (node (ref "EPD_C11") (pin "1") (pinfunction "1_1") (pintype "passive"))
      (node (ref "J3") (pin "23") (pinfunction "23_23") (pintype "bidirectional"))
    )
    (net (code "34") (name "Net-(EPD_C12-Pad1)") (class "Default")
      (node (ref "EPD_C12") (pin "1") (pinfunction "1_1") (pintype "passive"))
      (node (ref "J3") (pin "24") (pinfunction "24_24") (pintype "bidirectional"))
    )
    (net (code "35") (name "Net-(IC2-CT)") (class "Default")
      (node (ref "C_DELAY") (pin "1") (pinfunction "1_1") (pintype "passive"))
      (node (ref "IC2") (pin "5") (pinfunction "CT_5") (pintype "bidirectional"))
    )
    (net (code "36") (name "Net-(J2-PadA4)") (class "Default")
      (node (ref "J2") (pin "A4") (pinfunction "A4_A4") (pintype "bidirectional"))
      (node (ref "PFMF.050.1") (pin "1") (pinfunction "1_1") (pintype "passive"))
    )
    (net (code "37") (name "Net-(J2-PadA5)") (class "Default")
      (node (ref "J2") (pin "A5") (pinfunction "A5_A5") (pintype "bidirectional"))
      (node (ref "R2-USB1") (pin "2") (pinfunction "2_2") (pintype "passive"))
    )
    (net (code "38") (name "Net-(J2-PadB5)") (class "Default")
      (node (ref "J2") (pin "B5") (pinfunction "B5_B5") (pintype "bidirectional"))
      (node (ref "R2-USB") (pin "1") (pinfunction "1_1") (pintype "passive"))
    )
    (net (code "39") (name "Net-(U1-PROG)") (class "Default")
      (node (ref "R2_BAT") (pin "2") (pinfunction "2_2") (pintype "passive"))
      (node (ref "U1") (pin "5") (pinfunction "PROG_5") (pintype "input"))
    )
    (net (code "40") (name "Net-(U1-STAT)") (class "Default")
      (node (ref "R1_BAT") (pin "2") (pinfunction "2_2") (pintype "passive"))
      (node (ref "U1") (pin "1") (pinfunction "STAT_1") (pintype "output"))
    )
    (net (code "41") (name "PREVGH") (class "Default")
      (node (ref "D5") (pin "1") (pinfunction "K_1") (pintype "bidirectional"))
    )
    (net (code "42") (name "PREVGL") (class "Default")
      (node (ref "D3") (pin "2") (pinfunction "A_2") (pintype "bidirectional"))
    )
    (net (code "43") (name "RESE") (class "Default")
      (node (ref "J3") (pin "3") (pinfunction "3_3") (pintype "bidirectional"))
      (node (ref "Q2") (pin "2") (pinfunction "S_2") (pintype "bidirectional"))
      (node (ref "R3") (pin "2") (pinfunction "2_2") (pintype "passive"))
    )
    (net (code "44") (name "RESE'") (class "Default")
      (node (ref "R2") (pin "2") (pinfunction "2_2") (pintype "passive"))
      (node (ref "R3") (pin "1") (pinfunction "1_1") (pintype "passive"))
      (node (ref "SJ1") (pin "2") (pinfunction "2_2") (pintype "passive"))
    )
    (net (code "45") (name "RESET") (class "Default")
      (node (ref "C5") (pin "1") (pinfunction "1_1") (pintype "passive"))
      (node (ref "IC2") (pin "1") (pinfunction "VOUT_1") (pintype "bidirectional"))
      (node (ref "R14") (pin "1") (pinfunction "1_1") (pintype "passive"))
      (node (ref "RESET_BUTTON") (pin "3") (pinfunction "3_3") (pintype "passive"))
      (node (ref "RESET_BUTTON") (pin "4") (pinfunction "4_4") (pintype "passive"))
      (node (ref "U2") (pin "3") (pinfunction "EN_3") (pintype "input"))
    )
    (net (code "46") (name "RTC_RST") (class "Default")
      (node (ref "U2") (pin "16") (pinfunction "IO18_16") (pintype "bidirectional"))
      (node (ref "U5") (pin "4") (pinfunction "~{RST}_4") (pintype "input"))
    )
    (net (code "47") (name "RX") (class "Default")
      (node (ref "TP2") (pin "TP") (pinfunction "TP_TP") (pintype "input"))
      (node (ref "U2") (pin "24") (pinfunction "RXD0/GPIO17_24") (pintype "bidirectional"))
    )
    (net (code "48") (name "SCK") (class "Default")
      (node (ref "D9") (pin "2") (pinfunction "2_2") (pintype "passive"))
      (node (ref "J1") (pin "P5") (pinfunction "CLK_P5") (pintype "bidirectional"))
      (node (ref "J3") (pin "13") (pinfunction "13_13") (pintype "bidirectional"))
      (node (ref "R6") (pin "1") (pinfunction "1_1") (pintype "passive"))
      (node (ref "TP8") (pin "TP") (pinfunction "TP_TP") (pintype "input"))
      (node (ref "U2") (pin "6") (pinfunction "IO6_6") (pintype "bidirectional"))
      (node (ref "U6") (pin "6") (pinfunction "CLK_6") (pintype "input"))
    )
    (net (code "49") (name "SCL") (class "Default")
      (node (ref "J4") (pin "4") (pinfunction "4_4") (pintype "passive"))
      (node (ref "R2-PINH") (pin "1") (pinfunction "1_1") (pintype "passive"))
      (node (ref "U2") (pin "20") (pinfunction "IO22_20") (pintype "bidirectional"))
      (node (ref "U3") (pin "4") (pinfunction "SCK_4") (pintype "input"))
      (node (ref "U4") (pin "7") (pinfunction "SCL_7") (pintype "input"))
      (node (ref "U5") (pin "16") (pinfunction "SCL_16") (pintype "input"))
    )
    (net (code "50") (name "SDA") (class "Default")
      (node (ref "J4") (pin "3") (pinfunction "3_3") (pintype "passive"))
      (node (ref "R1_PINH") (pin "1") (pinfunction "1_1") (pintype "passive"))
      (node (ref "U2") (pin "19") (pinfunction "IO21_19") (pintype "bidirectional"))
      (node (ref "U3") (pin "3") (pinfunction "SDI_3") (pintype "bidirectional"))
      (node (ref "U4") (pin "8") (pinfunction "SDA_8") (pintype "bidirectional"))
      (node (ref "U5") (pin "15") (pinfunction "SDA_15") (pintype "bidirectional"))
    )
    (net (code "51") (name "SRC") (class "Default")
      (node (ref "C4") (pin "2") (pinfunction "2_2") (pintype "passive"))
      (node (ref "D5") (pin "2") (pinfunction "A_2") (pintype "bidirectional"))
      (node (ref "L1") (pin "1") (pinfunction "1_1") (pintype "passive"))
      (node (ref "Q2") (pin "3") (pinfunction "D_3") (pintype "bidirectional"))
    )
    (net (code "52") (name "SS_SD") (class "Default")
      (node (ref "D12") (pin "2") (pinfunction "2_2") (pintype "passive"))
      (node (ref "J1") (pin "P2") (pinfunction "CD/DAT3_P2") (pintype "bidirectional"))
      (node (ref "R22") (pin "1") (pinfunction "1_1") (pintype "passive"))
      (node (ref "U2") (pin "4") (pinfunction "IO4_4") (pintype "bidirectional"))
    )
    (net (code "53") (name "TX") (class "Default")
      (node (ref "TP1") (pin "TP") (pinfunction "TP_TP") (pintype "input"))
      (node (ref "U2") (pin "25") (pinfunction "TXD0/GPIO16_25") (pintype "bidirectional"))
    )
    (net (code "54") (name "USB_D+") (class "Default")
      (node (ref "D1") (pin "4") (pinfunction "I/O2_2_4") (pintype "bidirectional"))
      (node (ref "U2") (pin "14") (pinfunction "IO13_14") (pintype "bidirectional"))
    )
    (net (code "55") (name "USB_D-") (class "Default")
      (node (ref "D1") (pin "6") (pinfunction "I/O1_2_6") (pintype "bidirectional"))
      (node (ref "U2") (pin "13") (pinfunction "IO12_13") (pintype "bidirectional"))
    )
    (net (code "56") (name "VBAT") (class "Default")
      (node (ref "C2_BAT") (pin "1") (pinfunction "1_1") (pintype "passive"))
      (node (ref "Q1") (pin "3") (pinfunction "D_3") (pintype "bidirectional"))
      (node (ref "TP3") (pin "TP") (pinfunction "TP_TP") (pintype "input"))
      (node (ref "U1") (pin "3") (pinfunction "VBAT_3") (pintype "power_in"))
      (node (ref "U4") (pin "2") (pinfunction "CELL_2") (pintype "power_in"))
      (node (ref "U4") (pin "3") (pinfunction "VDD_3") (pintype "power_in"))
    )
    (net (code "57") (name "VBUS") (class "Default")
      (node (ref "C1_BAT") (pin "1") (pinfunction "1_1") (pintype "passive"))
      (node (ref "C4_USB") (pin "1") (pinfunction "1_1") (pintype "passive"))
      (node (ref "C5_USB") (pin "1") (pinfunction "1_1") (pintype "passive"))
      (node (ref "CHG_LED") (pin "A") (pinfunction "A_A") (pintype "passive"))
      (node (ref "D1") (pin "2") (pinfunction "GND_2") (pintype "bidirectional"))
      (node (ref "D2") (pin "2") (pinfunction "ANODE_2") (pintype "bidirectional"))
      (node (ref "PFMF.050.1") (pin "2") (pinfunction "2_2") (pintype "passive"))
      (node (ref "Q1") (pin "1") (pinfunction "G_1") (pintype "bidirectional"))
      (node (ref "R1_PWRUSB") (pin "2") (pinfunction "2_2") (pintype "passive"))
      (node (ref "TP14") (pin "TP") (pinfunction "TP_TP") (pintype "input"))
      (node (ref "U1") (pin "4") (pinfunction "VIN_4") (pintype "power_in"))
    )
    (net (code "58") (name "VRTC") (class "Default")
      (node (ref "C8") (pin "1") (pinfunction "1_1") (pintype "passive"))
      (node (ref "C9") (pin "1") (pinfunction "1_1") (pintype "passive"))
      (node (ref "R_CAPACITOR") (pin "2") (pinfunction "2_2") (pintype "passive"))
      (node (ref "U5") (pin "14") (pinfunction "VBAT_14") (pintype "power_in"))
    )
    (net (code "59") (name "VUSB") (class "Default")
      (node (ref "J2") (pin "A9") (pinfunction "A9_A9") (pintype "bidirectional"))
      (node (ref "J2") (pin "B4") (pinfunction "B4_B4") (pintype "bidirectional"))
      (node (ref "J2") (pin "B9") (pinfunction "B9_B9") (pintype "bidirectional"))
    )
    (net (code "60") (name "unconnected-(IC1-NC-Pad4)") (class "Default")
      (node (ref "IC1") (pin "4") (pinfunction "NC_4") (pintype "no_connect"))
    )
    (net (code "61") (name "unconnected-(IC2-NC-Pad4)") (class "Default")
      (node (ref "IC2") (pin "4") (pinfunction "NC_4") (pintype "no_connect"))
    )
    (net (code "62") (name "unconnected-(J1-DAT1-PadP8)") (class "Default")
      (node (ref "J1") (pin "P8") (pinfunction "DAT1_P8") (pintype "bidirectional"))
    )
    (net (code "63") (name "unconnected-(J1-DAT2-PadP1)") (class "Default")
      (node (ref "J1") (pin "P1") (pinfunction "DAT2_P1") (pintype "bidirectional"))
    )
    (net (code "64") (name "unconnected-(J1-DETECTION_1-PadS1)") (class "Default")
      (node (ref "J1") (pin "S1") (pinfunction "DETECTION_1_S1") (pintype "bidirectional"))
    )
    (net (code "65") (name "unconnected-(J1-DETECTION_2-PadS2)") (class "Default")
      (node (ref "J1") (pin "S2") (pinfunction "DETECTION_2_S2") (pintype "bidirectional"))
    )
    (net (code "66") (name "unconnected-(J2-PadA8)") (class "Default")
      (node (ref "J2") (pin "A8") (pinfunction "A8_A8") (pintype "bidirectional"))
    )
    (net (code "67") (name "unconnected-(J2-PadB8)") (class "Default")
      (node (ref "J2") (pin "B8") (pinfunction "B8_B8") (pintype "bidirectional"))
    )
    (net (code "68") (name "unconnected-(J3-Pad1)") (class "Default")
      (node (ref "J3") (pin "1") (pinfunction "1_1") (pintype "bidirectional"))
    )
    (net (code "69") (name "unconnected-(J3-Pad6)") (class "Default")
      (node (ref "J3") (pin "6") (pinfunction "6_6") (pintype "bidirectional"))
    )
    (net (code "70") (name "unconnected-(J3-Pad7)") (class "Default")
      (node (ref "J3") (pin "7") (pinfunction "7_7") (pintype "bidirectional"))
    )
    (net (code "71") (name "unconnected-(U2-NC-Pad22)") (class "Default")
      (node (ref "U2") (pin "22") (pinfunction "NC_22") (pintype "no_connect"))
    )
    (net (code "72") (name "unconnected-(U4-~{ALERT}-Pad5)") (class "Default")
      (node (ref "U4") (pin "5") (pinfunction "~{ALERT}_5") (pintype "output"))
    )
  )
)
